# SuperCapacitor_Schmatic_V2.net
KiCad netlist of a schematic drawn in EAGLE
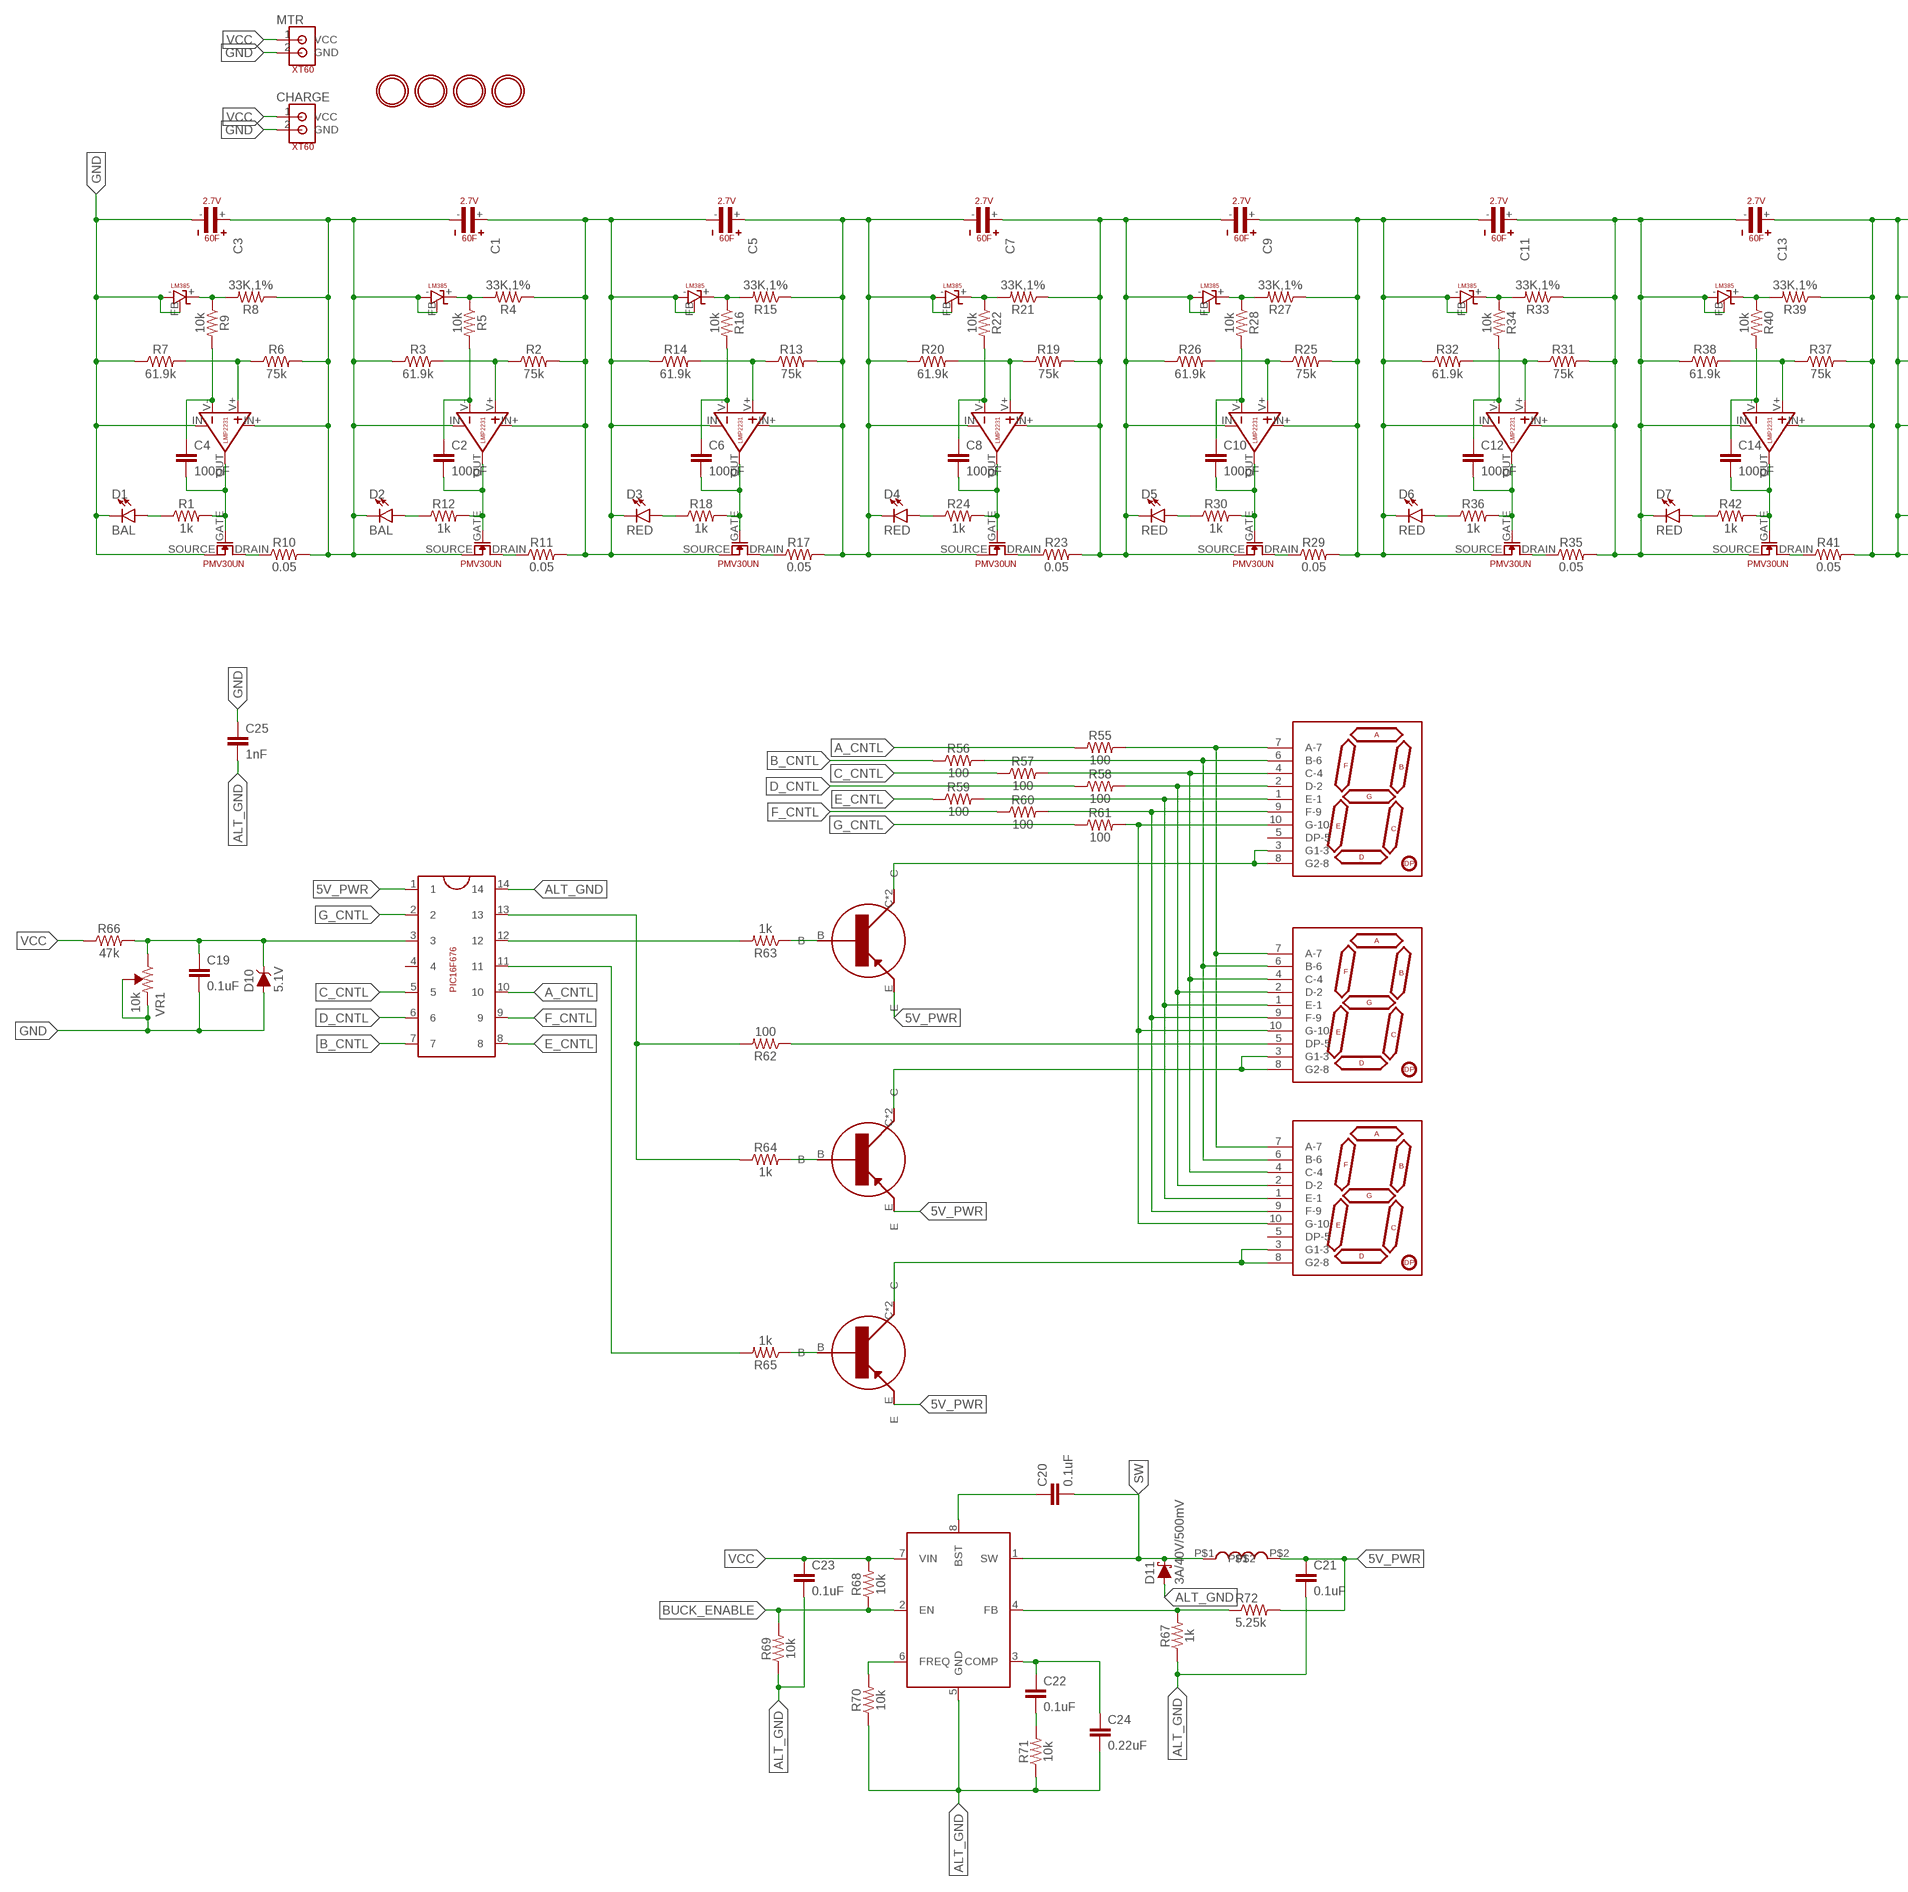
[diagram p0: schematic, sheet 1, part 1 of 2]
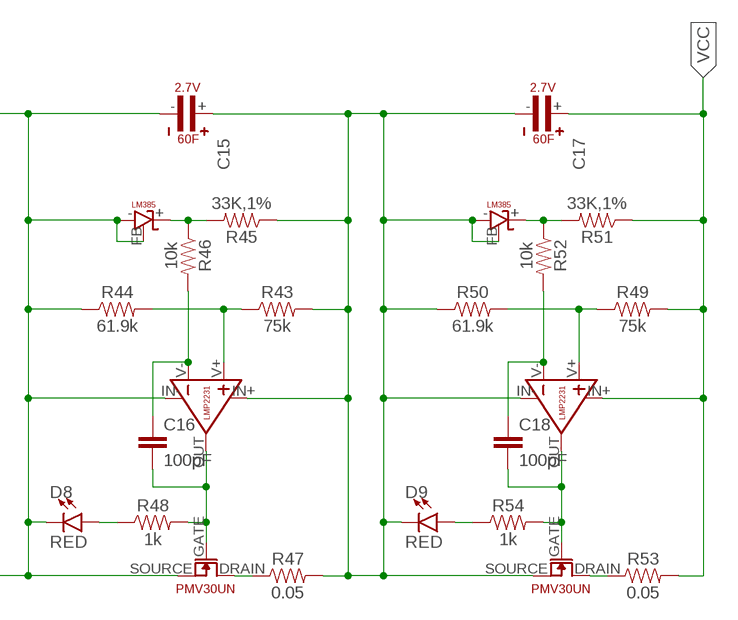
[diagram p1: schematic, sheet 1, part 2 of 2]

(export (version "E")
  (design (tool "Eeschema 10.0.6"))
  (components
    (comp (ref "3.3V_BUCK")
      (value "SOIC8E")
      (footprint "eagle-import:SOIC127P600X170-9N")
      (libsource (lib "eagle-import") (part "SOIC8E"))
    )
    (comp (ref "C1")
      (value "2.7V 60F")
      (footprint "eagle-import:2.7V_60F")
      (libsource (lib "eagle-import") (part "2.7V_60F"))
    )
    (comp (ref "C2")
      (value "100pF")
      (footprint "eagle-import:0603")
      (libsource (lib "eagle-import") (part "100PF-0603-50V-5%"))
    )
    (comp (ref "C3")
      (value "2.7V 60F")
      (footprint "eagle-import:2.7V_60F")
      (libsource (lib "eagle-import") (part "2.7V_60F"))
    )
    (comp (ref "C4")
      (value "100pF")
      (footprint "eagle-import:0603")
      (libsource (lib "eagle-import") (part "100PF-0603-50V-5%"))
    )
    (comp (ref "C5")
      (value "2.7V 60F")
      (footprint "eagle-import:2.7V_60F")
      (libsource (lib "eagle-import") (part "2.7V_60F"))
    )
    (comp (ref "C6")
      (value "100pF")
      (footprint "eagle-import:0603")
      (libsource (lib "eagle-import") (part "100PF-0603-50V-5%"))
    )
    (comp (ref "C7")
      (value "2.7V 60F")
      (footprint "eagle-import:2.7V_60F")
      (libsource (lib "eagle-import") (part "2.7V_60F"))
    )
    (comp (ref "C8")
      (value "100pF")
      (footprint "eagle-import:0603")
      (libsource (lib "eagle-import") (part "100PF-0603-50V-5%"))
    )
    (comp (ref "C9")
      (value "2.7V 60F")
      (footprint "eagle-import:2.7V_60F")
      (libsource (lib "eagle-import") (part "2.7V_60F"))
    )
    (comp (ref "C10")
      (value "100pF")
      (footprint "eagle-import:0603")
      (libsource (lib "eagle-import") (part "100PF-0603-50V-5%"))
    )
    (comp (ref "C11")
      (value "2.7V 60F")
      (footprint "eagle-import:2.7V_60F")
      (libsource (lib "eagle-import") (part "2.7V_60F"))
    )
    (comp (ref "C12")
      (value "100pF")
      (footprint "eagle-import:0603")
      (libsource (lib "eagle-import") (part "100PF-0603-50V-5%"))
    )
    (comp (ref "C13")
      (value "2.7V 60F")
      (footprint "eagle-import:2.7V_60F")
      (libsource (lib "eagle-import") (part "2.7V_60F"))
    )
    (comp (ref "C14")
      (value "100pF")
      (footprint "eagle-import:0603")
      (libsource (lib "eagle-import") (part "100PF-0603-50V-5%"))
    )
    (comp (ref "C15")
      (value "2.7V 60F")
      (footprint "eagle-import:2.7V_60F")
      (libsource (lib "eagle-import") (part "2.7V_60F"))
    )
    (comp (ref "C16")
      (value "100pF")
      (footprint "eagle-import:0603")
      (libsource (lib "eagle-import") (part "100PF-0603-50V-5%"))
    )
    (comp (ref "C17")
      (value "2.7V 60F")
      (footprint "eagle-import:2.7V_60F")
      (libsource (lib "eagle-import") (part "2.7V_60F"))
    )
    (comp (ref "C18")
      (value "100pF")
      (footprint "eagle-import:0603")
      (libsource (lib "eagle-import") (part "100PF-0603-50V-5%"))
    )
    (comp (ref "C19")
      (value "0.1uF")
      (footprint "eagle-import:0603")
      (libsource (lib "eagle-import") (part "SparkFun-Capacitors_510_0.1UF-0603-25V-5%"))
    )
    (comp (ref "C20")
      (value "0.1uF")
      (footprint "eagle-import:0603")
      (libsource (lib "eagle-import") (part "0.1UF-0603-25V-(+80/-20%)"))
    )
    (comp (ref "C21")
      (value "0.1uF")
      (footprint "eagle-import:0603")
      (libsource (lib "eagle-import") (part "0.1UF-0603-25V-(+80/-20%)"))
    )
    (comp (ref "C22")
      (value "0.1uF")
      (footprint "eagle-import:0603")
      (libsource (lib "eagle-import") (part "0.1UF-0603-25V-(+80/-20%)"))
    )
    (comp (ref "C23")
      (value "0.1uF")
      (footprint "eagle-import:0603")
      (libsource (lib "eagle-import") (part "0.1UF-0603-25V-(+80/-20%)"))
    )
    (comp (ref "C24")
      (value "0.22uF")
      (footprint "eagle-import:0603")
      (libsource (lib "eagle-import") (part "0.22UF-0603-50V-(-20/+80%)"))
    )
    (comp (ref "C25")
      (value "1nF")
      (footprint "eagle-import:0603")
      (libsource (lib "eagle-import") (part "1.0NF/1000PF-0603-50V-10%"))
    )
    (comp (ref "CHARGE")
      (value "XT60")
      (footprint "eagle-import:XT60")
      (libsource (lib "eagle-import") (part "XT60"))
    )
    (comp (ref "D1")
      (value "BAL")
      (footprint "eagle-import:LED-0603")
      (libsource (lib "eagle-import") (part "LED-RED0603"))
    )
    (comp (ref "D2")
      (value "BAL")
      (footprint "eagle-import:LED-0603")
      (libsource (lib "eagle-import") (part "LED-RED0603"))
    )
    (comp (ref "D3")
      (value "RED")
      (footprint "eagle-import:LED-0603")
      (libsource (lib "eagle-import") (part "LED-RED0603"))
    )
    (comp (ref "D4")
      (value "RED")
      (footprint "eagle-import:LED-0603")
      (libsource (lib "eagle-import") (part "LED-RED0603"))
    )
    (comp (ref "D5")
      (value "RED")
      (footprint "eagle-import:LED-0603")
      (libsource (lib "eagle-import") (part "LED-RED0603"))
    )
    (comp (ref "D6")
      (value "RED")
      (footprint "eagle-import:LED-0603")
      (libsource (lib "eagle-import") (part "LED-RED0603"))
    )
    (comp (ref "D7")
      (value "RED")
      (footprint "eagle-import:LED-0603")
      (libsource (lib "eagle-import") (part "LED-RED0603"))
    )
    (comp (ref "D8")
      (value "RED")
      (footprint "eagle-import:LED-0603")
      (libsource (lib "eagle-import") (part "LED-RED0603"))
    )
    (comp (ref "D9")
      (value "RED")
      (footprint "eagle-import:LED-0603")
      (libsource (lib "eagle-import") (part "LED-RED0603"))
    )
    (comp (ref "D10")
      (value "5.1V")
      (footprint "eagle-import:SOD-323")
      (libsource (lib "eagle-import") (part "DIODE-ZENER-MMSZ5232BS"))
    )
    (comp (ref "D11")
      (value "3A/40V/500mV")
      (footprint "eagle-import:SMA-DIODE")
      (libsource (lib "eagle-import") (part "DIODE-SCHOTTKY-B340A"))
    )
    (comp (ref "MTR")
      (value "XT60")
      (footprint "eagle-import:XT60")
      (libsource (lib "eagle-import") (part "XT60"))
    )
    (comp (ref "R1")
      (value "1k")
      (footprint "eagle-import:0603")
      (libsource (lib "eagle-import") (part "SparkFun-Resistors_532_1KOHM-0603-1/10W-1%"))
    )
    (comp (ref "R2")
      (value "75k")
      (footprint "eagle-import:0603@1")
      (libsource (lib "eagle-import") (part "75KOHM-0603-1/10W-1%"))
    )
    (comp (ref "R3")
      (value "61.9k")
      (footprint "eagle-import:0603@1")
      (libsource (lib "eagle-import") (part "75KOHM-0603-1/10W-1%"))
    )
    (comp (ref "R4")
      (value "33K,1%")
      (footprint "eagle-import:0603@1")
      (libsource (lib "eagle-import") (part "1MOHM-0603-1/4W-5%"))
    )
    (comp (ref "R5")
      (value "10k")
      (footprint "eagle-import:0603")
      (libsource (lib "eagle-import") (part "10KOHM-0603-1/10W-1%"))
    )
    (comp (ref "R6")
      (value "75k")
      (footprint "eagle-import:0603@1")
      (libsource (lib "eagle-import") (part "75KOHM-0603-1/10W-1%"))
    )
    (comp (ref "R7")
      (value "61.9k")
      (footprint "eagle-import:0603@1")
      (libsource (lib "eagle-import") (part "75KOHM-0603-1/10W-1%"))
    )
    (comp (ref "R8")
      (value "33K,1%")
      (footprint "eagle-import:0603@1")
      (libsource (lib "eagle-import") (part "1MOHM-0603-1/4W-5%"))
    )
    (comp (ref "R9")
      (value "10k")
      (footprint "eagle-import:0603")
      (libsource (lib "eagle-import") (part "10KOHM-0603-1/10W-1%"))
    )
    (comp (ref "R10")
      (value "0.05")
      (footprint "eagle-import:2512")
      (libsource (lib "eagle-import") (part "0.05OHM-2512-3W-1%"))
    )
    (comp (ref "R11")
      (value "0.05")
      (footprint "eagle-import:2512")
      (libsource (lib "eagle-import") (part "0.05OHM-2512-3W-1%"))
    )
    (comp (ref "R12")
      (value "1k")
      (footprint "eagle-import:0603")
      (libsource (lib "eagle-import") (part "SparkFun-Resistors_532_1KOHM-0603-1/10W-1%"))
    )
    (comp (ref "R13")
      (value "75k")
      (footprint "eagle-import:0603@1")
      (libsource (lib "eagle-import") (part "75KOHM-0603-1/10W-1%"))
    )
    (comp (ref "R14")
      (value "61.9k")
      (footprint "eagle-import:0603@1")
      (libsource (lib "eagle-import") (part "75KOHM-0603-1/10W-1%"))
    )
    (comp (ref "R15")
      (value "33K,1%")
      (footprint "eagle-import:0603@1")
      (libsource (lib "eagle-import") (part "1MOHM-0603-1/4W-5%"))
    )
    (comp (ref "R16")
      (value "10k")
      (footprint "eagle-import:0603")
      (libsource (lib "eagle-import") (part "10KOHM-0603-1/10W-1%"))
    )
    (comp (ref "R17")
      (value "0.05")
      (footprint "eagle-import:2512")
      (libsource (lib "eagle-import") (part "0.05OHM-2512-3W-1%"))
    )
    (comp (ref "R18")
      (value "1k")
      (footprint "eagle-import:0603")
      (libsource (lib "eagle-import") (part "SparkFun-Resistors_532_1KOHM-0603-1/10W-1%"))
    )
    (comp (ref "R19")
      (value "75k")
      (footprint "eagle-import:0603@1")
      (libsource (lib "eagle-import") (part "75KOHM-0603-1/10W-1%"))
    )
    (comp (ref "R20")
      (value "61.9k")
      (footprint "eagle-import:0603@1")
      (libsource (lib "eagle-import") (part "75KOHM-0603-1/10W-1%"))
    )
    (comp (ref "R21")
      (value "33K,1%")
      (footprint "eagle-import:0603@1")
      (libsource (lib "eagle-import") (part "1MOHM-0603-1/4W-5%"))
    )
    (comp (ref "R22")
      (value "10k")
      (footprint "eagle-import:0603")
      (libsource (lib "eagle-import") (part "10KOHM-0603-1/10W-1%"))
    )
    (comp (ref "R23")
      (value "0.05")
      (footprint "eagle-import:2512")
      (libsource (lib "eagle-import") (part "0.05OHM-2512-3W-1%"))
    )
    (comp (ref "R24")
      (value "1k")
      (footprint "eagle-import:0603")
      (libsource (lib "eagle-import") (part "SparkFun-Resistors_532_1KOHM-0603-1/10W-1%"))
    )
    (comp (ref "R25")
      (value "75k")
      (footprint "eagle-import:0603@1")
      (libsource (lib "eagle-import") (part "75KOHM-0603-1/10W-1%"))
    )
    (comp (ref "R26")
      (value "61.9k")
      (footprint "eagle-import:0603@1")
      (libsource (lib "eagle-import") (part "75KOHM-0603-1/10W-1%"))
    )
    (comp (ref "R27")
      (value "33K,1%")
      (footprint "eagle-import:0603@1")
      (libsource (lib "eagle-import") (part "1MOHM-0603-1/4W-5%"))
    )
    (comp (ref "R28")
      (value "10k")
      (footprint "eagle-import:0603")
      (libsource (lib "eagle-import") (part "10KOHM-0603-1/10W-1%"))
    )
    (comp (ref "R29")
      (value "0.05")
      (footprint "eagle-import:2512")
      (libsource (lib "eagle-import") (part "0.05OHM-2512-3W-1%"))
    )
    (comp (ref "R30")
      (value "1k")
      (footprint "eagle-import:0603")
      (libsource (lib "eagle-import") (part "SparkFun-Resistors_532_1KOHM-0603-1/10W-1%"))
    )
    (comp (ref "R31")
      (value "75k")
      (footprint "eagle-import:0603@1")
      (libsource (lib "eagle-import") (part "75KOHM-0603-1/10W-1%"))
    )
    (comp (ref "R32")
      (value "61.9k")
      (footprint "eagle-import:0603@1")
      (libsource (lib "eagle-import") (part "75KOHM-0603-1/10W-1%"))
    )
    (comp (ref "R33")
      (value "33K,1%")
      (footprint "eagle-import:0603@1")
      (libsource (lib "eagle-import") (part "1MOHM-0603-1/4W-5%"))
    )
    (comp (ref "R34")
      (value "10k")
      (footprint "eagle-import:0603")
      (libsource (lib "eagle-import") (part "10KOHM-0603-1/10W-1%"))
    )
    (comp (ref "R35")
      (value "0.05")
      (footprint "eagle-import:2512")
      (libsource (lib "eagle-import") (part "0.05OHM-2512-3W-1%"))
    )
    (comp (ref "R36")
      (value "1k")
      (footprint "eagle-import:0603")
      (libsource (lib "eagle-import") (part "SparkFun-Resistors_532_1KOHM-0603-1/10W-1%"))
    )
    (comp (ref "R37")
      (value "75k")
      (footprint "eagle-import:0603@1")
      (libsource (lib "eagle-import") (part "75KOHM-0603-1/10W-1%"))
    )
    (comp (ref "R38")
      (value "61.9k")
      (footprint "eagle-import:0603@1")
      (libsource (lib "eagle-import") (part "75KOHM-0603-1/10W-1%"))
    )
    (comp (ref "R39")
      (value "33K,1%")
      (footprint "eagle-import:0603@1")
      (libsource (lib "eagle-import") (part "1MOHM-0603-1/4W-5%"))
    )
    (comp (ref "R40")
      (value "10k")
      (footprint "eagle-import:0603")
      (libsource (lib "eagle-import") (part "10KOHM-0603-1/10W-1%"))
    )
    (comp (ref "R41")
      (value "0.05")
      (footprint "eagle-import:2512")
      (libsource (lib "eagle-import") (part "0.05OHM-2512-3W-1%"))
    )
    (comp (ref "R42")
      (value "1k")
      (footprint "eagle-import:0603")
      (libsource (lib "eagle-import") (part "SparkFun-Resistors_532_1KOHM-0603-1/10W-1%"))
    )
    (comp (ref "R43")
      (value "75k")
      (footprint "eagle-import:0603@1")
      (libsource (lib "eagle-import") (part "75KOHM-0603-1/10W-1%"))
    )
    (comp (ref "R44")
      (value "61.9k")
      (footprint "eagle-import:0603@1")
      (libsource (lib "eagle-import") (part "75KOHM-0603-1/10W-1%"))
    )
    (comp (ref "R45")
      (value "33K,1%")
      (footprint "eagle-import:0603@1")
      (libsource (lib "eagle-import") (part "1MOHM-0603-1/4W-5%"))
    )
    (comp (ref "R46")
      (value "10k")
      (footprint "eagle-import:0603")
      (libsource (lib "eagle-import") (part "10KOHM-0603-1/10W-1%"))
    )
    (comp (ref "R47")
      (value "0.05")
      (footprint "eagle-import:2512")
      (libsource (lib "eagle-import") (part "0.05OHM-2512-3W-1%"))
    )
    (comp (ref "R48")
      (value "1k")
      (footprint "eagle-import:0603")
      (libsource (lib "eagle-import") (part "SparkFun-Resistors_532_1KOHM-0603-1/10W-1%"))
    )
    (comp (ref "R49")
      (value "75k")
      (footprint "eagle-import:0603@1")
      (libsource (lib "eagle-import") (part "75KOHM-0603-1/10W-1%"))
    )
    (comp (ref "R50")
      (value "61.9k")
      (footprint "eagle-import:0603@1")
      (libsource (lib "eagle-import") (part "75KOHM-0603-1/10W-1%"))
    )
    (comp (ref "R51")
      (value "33K,1%")
      (footprint "eagle-import:0603@1")
      (libsource (lib "eagle-import") (part "1MOHM-0603-1/4W-5%"))
    )
    (comp (ref "R52")
      (value "10k")
      (footprint "eagle-import:0603")
      (libsource (lib "eagle-import") (part "10KOHM-0603-1/10W-1%"))
    )
    (comp (ref "R53")
      (value "0.05")
      (footprint "eagle-import:2512")
      (libsource (lib "eagle-import") (part "0.05OHM-2512-3W-1%"))
    )
    (comp (ref "R54")
      (value "1k")
      (footprint "eagle-import:0603")
      (libsource (lib "eagle-import") (part "SparkFun-Resistors_532_1KOHM-0603-1/10W-1%"))
    )
    (comp (ref "R55")
      (value "100")
      (footprint "eagle-import:0603")
      (libsource (lib "eagle-import") (part "100OHM-0603-1/4W-5%"))
    )
    (comp (ref "R56")
      (value "100")
      (footprint "eagle-import:0603")
      (libsource (lib "eagle-import") (part "100OHM-0603-1/4W-5%"))
    )
    (comp (ref "R57")
      (value "100")
      (footprint "eagle-import:0603")
      (libsource (lib "eagle-import") (part "100OHM-0603-1/4W-5%"))
    )
    (comp (ref "R58")
      (value "100")
      (footprint "eagle-import:0603")
      (libsource (lib "eagle-import") (part "100OHM-0603-1/4W-5%"))
    )
    (comp (ref "R59")
      (value "100")
      (footprint "eagle-import:0603")
      (libsource (lib "eagle-import") (part "100OHM-0603-1/4W-5%"))
    )
    (comp (ref "R60")
      (value "100")
      (footprint "eagle-import:0603")
      (libsource (lib "eagle-import") (part "100OHM-0603-1/4W-5%"))
    )
    (comp (ref "R61")
      (value "100")
      (footprint "eagle-import:0603")
      (libsource (lib "eagle-import") (part "100OHM-0603-1/4W-5%"))
    )
    (comp (ref "R62")
      (value "100")
      (footprint "eagle-import:0603")
      (libsource (lib "eagle-import") (part "100OHM-0603-1/4W-5%"))
    )
    (comp (ref "R63")
      (value "1k")
      (footprint "eagle-import:0603")
      (libsource (lib "eagle-import") (part "SparkFun-Resistors_532_1KOHM-0603-1/10W-1%"))
    )
    (comp (ref "R64")
      (value "1k")
      (footprint "eagle-import:0603")
      (libsource (lib "eagle-import") (part "SparkFun-Resistors_532_1KOHM-0603-1/10W-1%"))
    )
    (comp (ref "R65")
      (value "1k")
      (footprint "eagle-import:0603")
      (libsource (lib "eagle-import") (part "SparkFun-Resistors_532_1KOHM-0603-1/10W-1%"))
    )
    (comp (ref "R66")
      (value "47k")
      (footprint "eagle-import:0603")
      (libsource (lib "eagle-import") (part "47KOHM-0603-1/10W-1%"))
    )
    (comp (ref "R67")
      (value "1k")
      (footprint "eagle-import:0603")
      (libsource (lib "eagle-import") (part "1KOHM-0603-1/10W-1%"))
    )
    (comp (ref "R68")
      (value "10k")
      (footprint "eagle-import:0603")
      (libsource (lib "eagle-import") (part "10KOHM-0603-1/10W-1%"))
    )
    (comp (ref "R69")
      (value "10k")
      (footprint "eagle-import:0603")
      (libsource (lib "eagle-import") (part "10KOHM-0603-1/10W-1%"))
    )
    (comp (ref "R70")
      (value "10k")
      (footprint "eagle-import:0603")
      (libsource (lib "eagle-import") (part "10KOHM-0603-1/10W-1%"))
    )
    (comp (ref "R71")
      (value "10k")
      (footprint "eagle-import:0603")
      (libsource (lib "eagle-import") (part "10KOHM-0603-1/10W-1%"))
    )
    (comp (ref "R72")
      (value "5.25k")
      (footprint "eagle-import:RES_0805")
      (fields
        (field (name "DIGIKEY_PART_NUMBER") "541-0.0ATR-ND")
        (field (name "MANUFACTURER") "Vishay Dale")
        (field (name "MPN") "CRCW08050000Z0EA")
        (field (name "CREATED_BY") "PCBLayout.com")
      )
      (libsource (lib "eagle-import") (part "CRCW08050000Z0EA"))
    )
    (comp (ref "U$1")
      (value "LMP2231")
      (footprint "eagle-import:LMP2231_SOT23_5")
      (libsource (lib "eagle-import") (part "LMP2231"))
    )
    (comp (ref "U$2")
      (value "LM385")
      (footprint "eagle-import:LM385_SOT23")
      (libsource (lib "eagle-import") (part "LM385"))
    )
    (comp (ref "U$3")
      (value "PMV30UN_MOS")
      (footprint "eagle-import:PMV30UN_SOT23")
      (libsource (lib "eagle-import") (part "PMV30UN_MOS"))
    )
    (comp (ref "U$4")
      (value "LMP2231")
      (footprint "eagle-import:LMP2231_SOT23_5")
      (libsource (lib "eagle-import") (part "LMP2231"))
    )
    (comp (ref "U$5")
      (value "LM385")
      (footprint "eagle-import:LM385_SOT23")
      (libsource (lib "eagle-import") (part "LM385"))
    )
    (comp (ref "U$6")
      (value "PMV30UN_MOS")
      (footprint "eagle-import:PMV30UN_SOT23")
      (libsource (lib "eagle-import") (part "PMV30UN_MOS"))
    )
    (comp (ref "U$7")
      (value "LMP2231")
      (footprint "eagle-import:LMP2231_SOT23_5")
      (libsource (lib "eagle-import") (part "LMP2231"))
    )
    (comp (ref "U$8")
      (value "LM385")
      (footprint "eagle-import:LM385_SOT23")
      (libsource (lib "eagle-import") (part "LM385"))
    )
    (comp (ref "U$9")
      (value "PMV30UN_MOS")
      (footprint "eagle-import:PMV30UN_SOT23")
      (libsource (lib "eagle-import") (part "PMV30UN_MOS"))
    )
    (comp (ref "U$10")
      (value "LMP2231")
      (footprint "eagle-import:LMP2231_SOT23_5")
      (libsource (lib "eagle-import") (part "LMP2231"))
    )
    (comp (ref "U$11")
      (value "LM385")
      (footprint "eagle-import:LM385_SOT23")
      (libsource (lib "eagle-import") (part "LM385"))
    )
    (comp (ref "U$12")
      (value "PMV30UN_MOS")
      (footprint "eagle-import:PMV30UN_SOT23")
      (libsource (lib "eagle-import") (part "PMV30UN_MOS"))
    )
    (comp (ref "U$13")
      (value "LMP2231")
      (footprint "eagle-import:LMP2231_SOT23_5")
      (libsource (lib "eagle-import") (part "LMP2231"))
    )
    (comp (ref "U$14")
      (value "LM385")
      (footprint "eagle-import:LM385_SOT23")
      (libsource (lib "eagle-import") (part "LM385"))
    )
    (comp (ref "U$15")
      (value "PMV30UN_MOS")
      (footprint "eagle-import:PMV30UN_SOT23")
      (libsource (lib "eagle-import") (part "PMV30UN_MOS"))
    )
    (comp (ref "U$16")
      (value "LMP2231")
      (footprint "eagle-import:LMP2231_SOT23_5")
      (libsource (lib "eagle-import") (part "LMP2231"))
    )
    (comp (ref "U$17")
      (value "LM385")
      (footprint "eagle-import:LM385_SOT23")
      (libsource (lib "eagle-import") (part "LM385"))
    )
    (comp (ref "U$18")
      (value "PMV30UN_MOS")
      (footprint "eagle-import:PMV30UN_SOT23")
      (libsource (lib "eagle-import") (part "PMV30UN_MOS"))
    )
    (comp (ref "U$19")
      (value "LMP2231")
      (footprint "eagle-import:LMP2231_SOT23_5")
      (libsource (lib "eagle-import") (part "LMP2231"))
    )
    (comp (ref "U$20")
      (value "LM385")
      (footprint "eagle-import:LM385_SOT23")
      (libsource (lib "eagle-import") (part "LM385"))
    )
    (comp (ref "U$21")
      (value "PMV30UN_MOS")
      (footprint "eagle-import:PMV30UN_SOT23")
      (libsource (lib "eagle-import") (part "PMV30UN_MOS"))
    )
    (comp (ref "U$22")
      (value "LMP2231")
      (footprint "eagle-import:LMP2231_SOT23_5")
      (libsource (lib "eagle-import") (part "LMP2231"))
    )
    (comp (ref "U$23")
      (value "LM385")
      (footprint "eagle-import:LM385_SOT23")
      (libsource (lib "eagle-import") (part "LM385"))
    )
    (comp (ref "U$24")
      (value "PMV30UN_MOS")
      (footprint "eagle-import:PMV30UN_SOT23")
      (libsource (lib "eagle-import") (part "PMV30UN_MOS"))
    )
    (comp (ref "U$25")
      (value "LMP2231")
      (footprint "eagle-import:LMP2231_SOT23_5")
      (libsource (lib "eagle-import") (part "LMP2231"))
    )
    (comp (ref "U$26")
      (value "LM385")
      (footprint "eagle-import:LM385_SOT23")
      (libsource (lib "eagle-import") (part "LM385"))
    )
    (comp (ref "U$27")
      (value "PMV30UN_MOS")
      (footprint "eagle-import:PMV30UN_SOT23")
      (libsource (lib "eagle-import") (part "PMV30UN_MOS"))
    )
    (comp (ref "U$28")
      (value "PZT3906")
      (footprint "eagle-import:SOT_223")
      (libsource (lib "eagle-import") (part "PZT3906"))
    )
    (comp (ref "U$29")
      (value "PZT3906")
      (footprint "eagle-import:SOT_223")
      (libsource (lib "eagle-import") (part "PZT3906"))
    )
    (comp (ref "U$30")
      (value "M5")
      (footprint "eagle-import:M5")
      (libsource (lib "eagle-import") (part "M5"))
    )
    (comp (ref "U$31")
      (value "M5")
      (footprint "eagle-import:M5")
      (libsource (lib "eagle-import") (part "M5"))
    )
    (comp (ref "U$32")
      (value "M5")
      (footprint "eagle-import:M5")
      (libsource (lib "eagle-import") (part "M5"))
    )
    (comp (ref "U$33")
      (value "M5")
      (footprint "eagle-import:M5")
      (libsource (lib "eagle-import") (part "M5"))
    )
    (comp (ref "U$34")
      (value "PZT3906")
      (footprint "eagle-import:SOT_223")
      (libsource (lib "eagle-import") (part "PZT3906"))
    )
    (comp (ref "U$35")
      (value "DSM7T")
      (footprint "eagle-import:7-SEGMENT_SMD")
      (libsource (lib "eagle-import") (part "DSM7T"))
    )
    (comp (ref "U$36")
      (value "DSM7T")
      (footprint "eagle-import:7-SEGMENT_SMD")
      (libsource (lib "eagle-import") (part "DSM7T"))
    )
    (comp (ref "U$37")
      (value "DSM7T")
      (footprint "eagle-import:7-SEGMENT_SMD")
      (libsource (lib "eagle-import") (part "DSM7T"))
    )
    (comp (ref "U$38")
      (value "PIC16F676")
      (footprint "eagle-import:PIC16F676")
      (libsource (lib "eagle-import") (part "PIC16F676"))
    )
    (comp (ref "U$39")
      (value "4.7UH_INDUCTOR")
      (footprint "eagle-import:4.7UH_INDUCTOR")
      (libsource (lib "eagle-import") (part "4.7UH_INDUCTOR"))
    )
    (comp (ref "VR1")
      (value "10k")
      (footprint "eagle-import:TRIMPOT-SMD-TC33X")
      (libsource (lib "eagle-import") (part "TRIMPOT-SMD-3MM-OPEN-1/10W-25%"))
    )
  )
  (nets
    (net (code "1") (name "5V_PWR") (class "Default")
      (node (ref "C21") (pin "1") (pinfunction "1_1") (pintype "passive"))
      (node (ref "R72") (pin "2") (pinfunction "2_2") (pintype "passive"))
      (node (ref "U$28") (pin "E") (pinfunction "E_E") (pintype "bidirectional"))
      (node (ref "U$29") (pin "E") (pinfunction "E_E") (pintype "bidirectional"))
      (node (ref "U$34") (pin "E") (pinfunction "E_E") (pintype "bidirectional"))
      (node (ref "U$38") (pin "1") (pinfunction "1_1") (pintype "bidirectional"))
      (node (ref "U$39") (pin "P$2") (pinfunction "P$2_P$2") (pintype "bidirectional"))
    )
    (net (code "2") (name "ALT_GND") (class "Default")
      (node (ref "3.3V_BUCK") (pin "5") (pinfunction "GND_5") (pintype "bidirectional"))
      (node (ref "C21") (pin "2") (pinfunction "2_2") (pintype "passive"))
      (node (ref "C23") (pin "2") (pinfunction "2_2") (pintype "passive"))
      (node (ref "C24") (pin "2") (pinfunction "2_2") (pintype "passive"))
      (node (ref "C25") (pin "2") (pinfunction "2_2") (pintype "passive"))
      (node (ref "D11") (pin "A") (pinfunction "A_A") (pintype "passive"))
      (node (ref "R67") (pin "1") (pinfunction "1_1") (pintype "passive"))
      (node (ref "R69") (pin "1") (pinfunction "1_1") (pintype "passive"))
      (node (ref "R70") (pin "1") (pinfunction "1_1") (pintype "passive"))
      (node (ref "R71") (pin "1") (pinfunction "1_1") (pintype "passive"))
      (node (ref "U$38") (pin "14") (pinfunction "14_14") (pintype "bidirectional"))
    )
    (net (code "3") (name "A_CNTL") (class "Default")
      (node (ref "R55") (pin "1") (pinfunction "1_1") (pintype "passive"))
      (node (ref "U$38") (pin "10") (pinfunction "10_10") (pintype "bidirectional"))
    )
    (net (code "4") (name "BUCK_ENABLE") (class "Default")
      (node (ref "3.3V_BUCK") (pin "2") (pinfunction "EN_2") (pintype "bidirectional"))
      (node (ref "R68") (pin "1") (pinfunction "1_1") (pintype "passive"))
      (node (ref "R69") (pin "2") (pinfunction "2_2") (pintype "passive"))
    )
    (net (code "5") (name "B_CNTL") (class "Default")
      (node (ref "R56") (pin "1") (pinfunction "1_1") (pintype "passive"))
      (node (ref "U$38") (pin "7") (pinfunction "7_7") (pintype "bidirectional"))
    )
    (net (code "6") (name "C_CNTL") (class "Default")
      (node (ref "R57") (pin "1") (pinfunction "1_1") (pintype "passive"))
      (node (ref "U$38") (pin "5") (pinfunction "5_5") (pintype "bidirectional"))
    )
    (net (code "7") (name "D_CNTL") (class "Default")
      (node (ref "R58") (pin "1") (pinfunction "1_1") (pintype "passive"))
      (node (ref "U$38") (pin "6") (pinfunction "6_6") (pintype "bidirectional"))
    )
    (net (code "8") (name "E_CNTL") (class "Default")
      (node (ref "R59") (pin "1") (pinfunction "1_1") (pintype "passive"))
      (node (ref "U$38") (pin "8") (pinfunction "8_8") (pintype "bidirectional"))
    )
    (net (code "9") (name "F_CNTL") (class "Default")
      (node (ref "R60") (pin "1") (pinfunction "1_1") (pintype "passive"))
      (node (ref "U$38") (pin "9") (pinfunction "9_9") (pintype "bidirectional"))
    )
    (net (code "10") (name "GND") (class "Default")
      (node (ref "C19") (pin "2") (pinfunction "2_2") (pintype "passive"))
      (node (ref "C25") (pin "1") (pinfunction "1_1") (pintype "passive"))
      (node (ref "C3") (pin "-") (pinfunction "-_-") (pintype "bidirectional"))
      (node (ref "CHARGE") (pin "2") (pinfunction "GND_2") (pintype "bidirectional"))
      (node (ref "D1") (pin "C") (pinfunction "C_C") (pintype "passive"))
      (node (ref "D10") (pin "A") (pinfunction "A_A") (pintype "passive"))
      (node (ref "MTR") (pin "2") (pinfunction "GND_2") (pintype "bidirectional"))
      (node (ref "R7") (pin "1") (pinfunction "1_1") (pintype "passive"))
      (node (ref "U$4") (pin "IN-") (pinfunction "IN-_IN-") (pintype "bidirectional"))
      (node (ref "U$5") (pin "-") (pinfunction "-_-") (pintype "bidirectional"))
      (node (ref "U$5") (pin "FB") (pinfunction "FB_FB") (pintype "bidirectional"))
      (node (ref "U$6") (pin "SOURCE") (pinfunction "SOURCE_SOURCE") (pintype "bidirectional"))
      (node (ref "VR1") (pin "2") (pinfunction "WIPER_2") (pintype "passive"))
      (node (ref "VR1") (pin "3") (pinfunction "CCW_3") (pintype "passive"))
    )
    (net (code "11") (name "G_CNTL") (class "Default")
      (node (ref "R61") (pin "1") (pinfunction "1_1") (pintype "passive"))
      (node (ref "U$38") (pin "2") (pinfunction "2_2") (pintype "bidirectional"))
    )
    (net (code "12") (name "Net-(3.3V_BUCK-BST)") (class "Default")
      (node (ref "3.3V_BUCK") (pin "8") (pinfunction "BST_8") (pintype "bidirectional"))
      (node (ref "C20") (pin "1") (pinfunction "1_1") (pintype "passive"))
    )
    (net (code "13") (name "Net-(3.3V_BUCK-COMP)") (class "Default")
      (node (ref "3.3V_BUCK") (pin "3") (pinfunction "COMP_3") (pintype "bidirectional"))
      (node (ref "C22") (pin "1") (pinfunction "1_1") (pintype "passive"))
      (node (ref "C24") (pin "1") (pinfunction "1_1") (pintype "passive"))
    )
    (net (code "14") (name "Net-(3.3V_BUCK-FB)") (class "Default")
      (node (ref "3.3V_BUCK") (pin "4") (pinfunction "FB_4") (pintype "bidirectional"))
      (node (ref "R67") (pin "2") (pinfunction "2_2") (pintype "passive"))
      (node (ref "R72") (pin "1") (pinfunction "1_1") (pintype "passive"))
    )
    (net (code "15") (name "Net-(3.3V_BUCK-FREQ)") (class "Default")
      (node (ref "3.3V_BUCK") (pin "6") (pinfunction "FREQ_6") (pintype "bidirectional"))
      (node (ref "R70") (pin "2") (pinfunction "2_2") (pintype "passive"))
    )
    (net (code "16") (name "Net-(C2-Pad1)") (class "Default")
      (node (ref "C2") (pin "1") (pinfunction "1_1") (pintype "passive"))
      (node (ref "R5") (pin "2") (pinfunction "2_2") (pintype "passive"))
      (node (ref "U$1") (pin "V-") (pinfunction "V-_V-") (pintype "bidirectional"))
    )
    (net (code "17") (name "Net-(C2-Pad2)") (class "Default")
      (node (ref "C2") (pin "2") (pinfunction "2_2") (pintype "passive"))
      (node (ref "R12") (pin "2") (pinfunction "2_2") (pintype "passive"))
      (node (ref "U$1") (pin "OUT") (pinfunction "OUT_OUT") (pintype "bidirectional"))
      (node (ref "U$3") (pin "GATE") (pinfunction "GATE_GATE") (pintype "bidirectional"))
    )
    (net (code "18") (name "Net-(C4-Pad1)") (class "Default")
      (node (ref "C4") (pin "1") (pinfunction "1_1") (pintype "passive"))
      (node (ref "R9") (pin "2") (pinfunction "2_2") (pintype "passive"))
      (node (ref "U$4") (pin "V-") (pinfunction "V-_V-") (pintype "bidirectional"))
    )
    (net (code "19") (name "Net-(C4-Pad2)") (class "Default")
      (node (ref "C4") (pin "2") (pinfunction "2_2") (pintype "passive"))
      (node (ref "R1") (pin "2") (pinfunction "2_2") (pintype "passive"))
      (node (ref "U$4") (pin "OUT") (pinfunction "OUT_OUT") (pintype "bidirectional"))
      (node (ref "U$6") (pin "GATE") (pinfunction "GATE_GATE") (pintype "bidirectional"))
    )
    (net (code "20") (name "Net-(C6-Pad1)") (class "Default")
      (node (ref "C6") (pin "1") (pinfunction "1_1") (pintype "passive"))
      (node (ref "R16") (pin "2") (pinfunction "2_2") (pintype "passive"))
      (node (ref "U$7") (pin "V-") (pinfunction "V-_V-") (pintype "bidirectional"))
    )
    (net (code "21") (name "Net-(C6-Pad2)") (class "Default")
      (node (ref "C6") (pin "2") (pinfunction "2_2") (pintype "passive"))
      (node (ref "R18") (pin "2") (pinfunction "2_2") (pintype "passive"))
      (node (ref "U$7") (pin "OUT") (pinfunction "OUT_OUT") (pintype "bidirectional"))
      (node (ref "U$9") (pin "GATE") (pinfunction "GATE_GATE") (pintype "bidirectional"))
    )
    (net (code "22") (name "Net-(C8-Pad1)") (class "Default")
      (node (ref "C8") (pin "1") (pinfunction "1_1") (pintype "passive"))
      (node (ref "R22") (pin "2") (pinfunction "2_2") (pintype "passive"))
      (node (ref "U$10") (pin "V-") (pinfunction "V-_V-") (pintype "bidirectional"))
    )
    (net (code "23") (name "Net-(C8-Pad2)") (class "Default")
      (node (ref "C8") (pin "2") (pinfunction "2_2") (pintype "passive"))
      (node (ref "R24") (pin "2") (pinfunction "2_2") (pintype "passive"))
      (node (ref "U$10") (pin "OUT") (pinfunction "OUT_OUT") (pintype "bidirectional"))
      (node (ref "U$12") (pin "GATE") (pinfunction "GATE_GATE") (pintype "bidirectional"))
    )
    (net (code "24") (name "Net-(C10-Pad1)") (class "Default")
      (node (ref "C10") (pin "1") (pinfunction "1_1") (pintype "passive"))
      (node (ref "R28") (pin "2") (pinfunction "2_2") (pintype "passive"))
      (node (ref "U$13") (pin "V-") (pinfunction "V-_V-") (pintype "bidirectional"))
    )
    (net (code "25") (name "Net-(C10-Pad2)") (class "Default")
      (node (ref "C10") (pin "2") (pinfunction "2_2") (pintype "passive"))
      (node (ref "R30") (pin "2") (pinfunction "2_2") (pintype "passive"))
      (node (ref "U$13") (pin "OUT") (pinfunction "OUT_OUT") (pintype "bidirectional"))
      (node (ref "U$15") (pin "GATE") (pinfunction "GATE_GATE") (pintype "bidirectional"))
    )
    (net (code "26") (name "Net-(C12-Pad1)") (class "Default")
      (node (ref "C12") (pin "1") (pinfunction "1_1") (pintype "passive"))
      (node (ref "R34") (pin "2") (pinfunction "2_2") (pintype "passive"))
      (node (ref "U$16") (pin "V-") (pinfunction "V-_V-") (pintype "bidirectional"))
    )
    (net (code "27") (name "Net-(C12-Pad2)") (class "Default")
      (node (ref "C12") (pin "2") (pinfunction "2_2") (pintype "passive"))
      (node (ref "R36") (pin "2") (pinfunction "2_2") (pintype "passive"))
      (node (ref "U$16") (pin "OUT") (pinfunction "OUT_OUT") (pintype "bidirectional"))
      (node (ref "U$18") (pin "GATE") (pinfunction "GATE_GATE") (pintype "bidirectional"))
    )
    (net (code "28") (name "Net-(C14-Pad1)") (class "Default")
      (node (ref "C14") (pin "1") (pinfunction "1_1") (pintype "passive"))
      (node (ref "R40") (pin "2") (pinfunction "2_2") (pintype "passive"))
      (node (ref "U$19") (pin "V-") (pinfunction "V-_V-") (pintype "bidirectional"))
    )
    (net (code "29") (name "Net-(C14-Pad2)") (class "Default")
      (node (ref "C14") (pin "2") (pinfunction "2_2") (pintype "passive"))
      (node (ref "R42") (pin "2") (pinfunction "2_2") (pintype "passive"))
      (node (ref "U$19") (pin "OUT") (pinfunction "OUT_OUT") (pintype "bidirectional"))
      (node (ref "U$21") (pin "GATE") (pinfunction "GATE_GATE") (pintype "bidirectional"))
    )
    (net (code "30") (name "Net-(C16-Pad1)") (class "Default")
      (node (ref "C16") (pin "1") (pinfunction "1_1") (pintype "passive"))
      (node (ref "R46") (pin "2") (pinfunction "2_2") (pintype "passive"))
      (node (ref "U$22") (pin "V-") (pinfunction "V-_V-") (pintype "bidirectional"))
    )
    (net (code "31") (name "Net-(C16-Pad2)") (class "Default")
      (node (ref "C16") (pin "2") (pinfunction "2_2") (pintype "passive"))
      (node (ref "R48") (pin "2") (pinfunction "2_2") (pintype "passive"))
      (node (ref "U$22") (pin "OUT") (pinfunction "OUT_OUT") (pintype "bidirectional"))
      (node (ref "U$24") (pin "GATE") (pinfunction "GATE_GATE") (pintype "bidirectional"))
    )
    (net (code "32") (name "Net-(C18-Pad1)") (class "Default")
      (node (ref "C18") (pin "1") (pinfunction "1_1") (pintype "passive"))
      (node (ref "R52") (pin "2") (pinfunction "2_2") (pintype "passive"))
      (node (ref "U$25") (pin "V-") (pinfunction "V-_V-") (pintype "bidirectional"))
    )
    (net (code "33") (name "Net-(C18-Pad2)") (class "Default")
      (node (ref "C18") (pin "2") (pinfunction "2_2") (pintype "passive"))
      (node (ref "R54") (pin "2") (pinfunction "2_2") (pintype "passive"))
      (node (ref "U$25") (pin "OUT") (pinfunction "OUT_OUT") (pintype "bidirectional"))
      (node (ref "U$27") (pin "GATE") (pinfunction "GATE_GATE") (pintype "bidirectional"))
    )
    (net (code "34") (name "Net-(C22-Pad2)") (class "Default")
      (node (ref "C22") (pin "2") (pinfunction "2_2") (pintype "passive"))
      (node (ref "R71") (pin "2") (pinfunction "2_2") (pintype "passive"))
    )
    (net (code "35") (name "Net-(D1-PadA)") (class "Default")
      (node (ref "D1") (pin "A") (pinfunction "A_A") (pintype "passive"))
      (node (ref "R1") (pin "1") (pinfunction "1_1") (pintype "passive"))
    )
    (net (code "36") (name "Net-(D2-PadA)") (class "Default")
      (node (ref "D2") (pin "A") (pinfunction "A_A") (pintype "passive"))
      (node (ref "R12") (pin "1") (pinfunction "1_1") (pintype "passive"))
    )
    (net (code "37") (name "Net-(D3-PadA)") (class "Default")
      (node (ref "D3") (pin "A") (pinfunction "A_A") (pintype "passive"))
      (node (ref "R18") (pin "1") (pinfunction "1_1") (pintype "passive"))
    )
    (net (code "38") (name "Net-(D4-PadA)") (class "Default")
      (node (ref "D4") (pin "A") (pinfunction "A_A") (pintype "passive"))
      (node (ref "R24") (pin "1") (pinfunction "1_1") (pintype "passive"))
    )
    (net (code "39") (name "Net-(D5-PadA)") (class "Default")
      (node (ref "D5") (pin "A") (pinfunction "A_A") (pintype "passive"))
      (node (ref "R30") (pin "1") (pinfunction "1_1") (pintype "passive"))
    )
    (net (code "40") (name "Net-(D6-PadA)") (class "Default")
      (node (ref "D6") (pin "A") (pinfunction "A_A") (pintype "passive"))
      (node (ref "R36") (pin "1") (pinfunction "1_1") (pintype "passive"))
    )
    (net (code "41") (name "Net-(D7-PadA)") (class "Default")
      (node (ref "D7") (pin "A") (pinfunction "A_A") (pintype "passive"))
      (node (ref "R42") (pin "1") (pinfunction "1_1") (pintype "passive"))
    )
    (net (code "42") (name "Net-(D8-PadA)") (class "Default")
      (node (ref "D8") (pin "A") (pinfunction "A_A") (pintype "passive"))
      (node (ref "R48") (pin "1") (pinfunction "1_1") (pintype "passive"))
    )
    (net (code "43") (name "Net-(D9-PadA)") (class "Default")
      (node (ref "D9") (pin "A") (pinfunction "A_A") (pintype "passive"))
      (node (ref "R54") (pin "1") (pinfunction "1_1") (pintype "passive"))
    )
    (net (code "44") (name "Net-(R2-Pad1)") (class "Default")
      (node (ref "R2") (pin "1") (pinfunction "1_1") (pintype "passive"))
      (node (ref "R3") (pin "2") (pinfunction "2_2") (pintype "passive"))
      (node (ref "U$1") (pin "V+") (pinfunction "V+_V+") (pintype "bidirectional"))
    )
    (net (code "45") (name "Net-(R4-Pad2)") (class "Default")
      (node (ref "R4") (pin "2") (pinfunction "2_2") (pintype "passive"))
      (node (ref "R5") (pin "1") (pinfunction "1_1") (pintype "passive"))
      (node (ref "U$2") (pin "+") (pinfunction "+_+") (pintype "bidirectional"))
    )
    (net (code "46") (name "Net-(R6-Pad1)") (class "Default")
      (node (ref "R6") (pin "1") (pinfunction "1_1") (pintype "passive"))
      (node (ref "R7") (pin "2") (pinfunction "2_2") (pintype "passive"))
      (node (ref "U$4") (pin "V+") (pinfunction "V+_V+") (pintype "bidirectional"))
    )
    (net (code "47") (name "Net-(R8-Pad2)") (class "Default")
      (node (ref "R8") (pin "2") (pinfunction "2_2") (pintype "passive"))
      (node (ref "R9") (pin "1") (pinfunction "1_1") (pintype "passive"))
      (node (ref "U$5") (pin "+") (pinfunction "+_+") (pintype "bidirectional"))
    )
    (net (code "48") (name "Net-(R10-1)") (class "Default")
      (node (ref "R10") (pin "P$1") (pinfunction "1_P$1") (pintype "passive"))
      (node (ref "U$6") (pin "DRAIN") (pinfunction "DRAIN_DRAIN") (pintype "bidirectional"))
    )
    (net (code "49") (name "Net-(R10-2)") (class "Default")
      (node (ref "C1") (pin "-") (pinfunction "-_-") (pintype "bidirectional"))
      (node (ref "C3") (pin "+") (pinfunction "+_+") (pintype "bidirectional"))
      (node (ref "D2") (pin "C") (pinfunction "C_C") (pintype "passive"))
      (node (ref "R10") (pin "P$2") (pinfunction "2_P$2") (pintype "passive"))
      (node (ref "R3") (pin "1") (pinfunction "1_1") (pintype "passive"))
      (node (ref "R6") (pin "2") (pinfunction "2_2") (pintype "passive"))
      (node (ref "R8") (pin "1") (pinfunction "1_1") (pintype "passive"))
      (node (ref "U$1") (pin "IN-") (pinfunction "IN-_IN-") (pintype "bidirectional"))
      (node (ref "U$2") (pin "-") (pinfunction "-_-") (pintype "bidirectional"))
      (node (ref "U$2") (pin "FB") (pinfunction "FB_FB") (pintype "bidirectional"))
      (node (ref "U$3") (pin "SOURCE") (pinfunction "SOURCE_SOURCE") (pintype "bidirectional"))
      (node (ref "U$4") (pin "IN+") (pinfunction "IN+_IN+") (pintype "bidirectional"))
    )
    (net (code "50") (name "Net-(R11-1)") (class "Default")
      (node (ref "R11") (pin "P$1") (pinfunction "1_P$1") (pintype "passive"))
      (node (ref "U$3") (pin "DRAIN") (pinfunction "DRAIN_DRAIN") (pintype "bidirectional"))
    )
    (net (code "51") (name "Net-(R11-2)") (class "Default")
      (node (ref "C1") (pin "+") (pinfunction "+_+") (pintype "bidirectional"))
      (node (ref "C5") (pin "-") (pinfunction "-_-") (pintype "bidirectional"))
      (node (ref "D3") (pin "C") (pinfunction "C_C") (pintype "passive"))
      (node (ref "R11") (pin "P$2") (pinfunction "2_P$2") (pintype "passive"))
      (node (ref "R14") (pin "1") (pinfunction "1_1") (pintype "passive"))
      (node (ref "R2") (pin "2") (pinfunction "2_2") (pintype "passive"))
      (node (ref "R4") (pin "1") (pinfunction "1_1") (pintype "passive"))
      (node (ref "U$1") (pin "IN+") (pinfunction "IN+_IN+") (pintype "bidirectional"))
      (node (ref "U$7") (pin "IN-") (pinfunction "IN-_IN-") (pintype "bidirectional"))
      (node (ref "U$8") (pin "-") (pinfunction "-_-") (pintype "bidirectional"))
      (node (ref "U$8") (pin "FB") (pinfunction "FB_FB") (pintype "bidirectional"))
      (node (ref "U$9") (pin "SOURCE") (pinfunction "SOURCE_SOURCE") (pintype "bidirectional"))
    )
    (net (code "52") (name "Net-(R13-Pad1)") (class "Default")
      (node (ref "R13") (pin "1") (pinfunction "1_1") (pintype "passive"))
      (node (ref "R14") (pin "2") (pinfunction "2_2") (pintype "passive"))
      (node (ref "U$7") (pin "V+") (pinfunction "V+_V+") (pintype "bidirectional"))
    )
    (net (code "53") (name "Net-(R15-Pad2)") (class "Default")
      (node (ref "R15") (pin "2") (pinfunction "2_2") (pintype "passive"))
      (node (ref "R16") (pin "1") (pinfunction "1_1") (pintype "passive"))
      (node (ref "U$8") (pin "+") (pinfunction "+_+") (pintype "bidirectional"))
    )
    (net (code "54") (name "Net-(R17-1)") (class "Default")
      (node (ref "R17") (pin "P$1") (pinfunction "1_P$1") (pintype "passive"))
      (node (ref "U$9") (pin "DRAIN") (pinfunction "DRAIN_DRAIN") (pintype "bidirectional"))
    )
    (net (code "55") (name "Net-(R17-2)") (class "Default")
      (node (ref "C5") (pin "+") (pinfunction "+_+") (pintype "bidirectional"))
      (node (ref "C7") (pin "-") (pinfunction "-_-") (pintype "bidirectional"))
      (node (ref "D4") (pin "C") (pinfunction "C_C") (pintype "passive"))
      (node (ref "R13") (pin "2") (pinfunction "2_2") (pintype "passive"))
      (node (ref "R15") (pin "1") (pinfunction "1_1") (pintype "passive"))
      (node (ref "R17") (pin "P$2") (pinfunction "2_P$2") (pintype "passive"))
      (node (ref "R20") (pin "1") (pinfunction "1_1") (pintype "passive"))
      (node (ref "U$10") (pin "IN-") (pinfunction "IN-_IN-") (pintype "bidirectional"))
      (node (ref "U$11") (pin "-") (pinfunction "-_-") (pintype "bidirectional"))
      (node (ref "U$11") (pin "FB") (pinfunction "FB_FB") (pintype "bidirectional"))
      (node (ref "U$12") (pin "SOURCE") (pinfunction "SOURCE_SOURCE") (pintype "bidirectional"))
      (node (ref "U$7") (pin "IN+") (pinfunction "IN+_IN+") (pintype "bidirectional"))
    )
    (net (code "56") (name "Net-(R19-Pad1)") (class "Default")
      (node (ref "R19") (pin "1") (pinfunction "1_1") (pintype "passive"))
      (node (ref "R20") (pin "2") (pinfunction "2_2") (pintype "passive"))
      (node (ref "U$10") (pin "V+") (pinfunction "V+_V+") (pintype "bidirectional"))
    )
    (net (code "57") (name "Net-(R21-Pad2)") (class "Default")
      (node (ref "R21") (pin "2") (pinfunction "2_2") (pintype "passive"))
      (node (ref "R22") (pin "1") (pinfunction "1_1") (pintype "passive"))
      (node (ref "U$11") (pin "+") (pinfunction "+_+") (pintype "bidirectional"))
    )
    (net (code "58") (name "Net-(R23-1)") (class "Default")
      (node (ref "R23") (pin "P$1") (pinfunction "1_P$1") (pintype "passive"))
      (node (ref "U$12") (pin "DRAIN") (pinfunction "DRAIN_DRAIN") (pintype "bidirectional"))
    )
    (net (code "59") (name "Net-(R23-2)") (class "Default")
      (node (ref "C7") (pin "+") (pinfunction "+_+") (pintype "bidirectional"))
      (node (ref "C9") (pin "-") (pinfunction "-_-") (pintype "bidirectional"))
      (node (ref "D5") (pin "C") (pinfunction "C_C") (pintype "passive"))
      (node (ref "R19") (pin "2") (pinfunction "2_2") (pintype "passive"))
      (node (ref "R21") (pin "1") (pinfunction "1_1") (pintype "passive"))
      (node (ref "R23") (pin "P$2") (pinfunction "2_P$2") (pintype "passive"))
      (node (ref "R26") (pin "1") (pinfunction "1_1") (pintype "passive"))
      (node (ref "U$10") (pin "IN+") (pinfunction "IN+_IN+") (pintype "bidirectional"))
      (node (ref "U$13") (pin "IN-") (pinfunction "IN-_IN-") (pintype "bidirectional"))
      (node (ref "U$14") (pin "-") (pinfunction "-_-") (pintype "bidirectional"))
      (node (ref "U$14") (pin "FB") (pinfunction "FB_FB") (pintype "bidirectional"))
      (node (ref "U$15") (pin "SOURCE") (pinfunction "SOURCE_SOURCE") (pintype "bidirectional"))
    )
    (net (code "60") (name "Net-(R25-Pad1)") (class "Default")
      (node (ref "R25") (pin "1") (pinfunction "1_1") (pintype "passive"))
      (node (ref "R26") (pin "2") (pinfunction "2_2") (pintype "passive"))
      (node (ref "U$13") (pin "V+") (pinfunction "V+_V+") (pintype "bidirectional"))
    )
    (net (code "61") (name "Net-(R27-Pad2)") (class "Default")
      (node (ref "R27") (pin "2") (pinfunction "2_2") (pintype "passive"))
      (node (ref "R28") (pin "1") (pinfunction "1_1") (pintype "passive"))
      (node (ref "U$14") (pin "+") (pinfunction "+_+") (pintype "bidirectional"))
    )
    (net (code "62") (name "Net-(R29-1)") (class "Default")
      (node (ref "R29") (pin "P$1") (pinfunction "1_P$1") (pintype "passive"))
      (node (ref "U$15") (pin "DRAIN") (pinfunction "DRAIN_DRAIN") (pintype "bidirectional"))
    )
    (net (code "63") (name "Net-(R29-2)") (class "Default")
      (node (ref "C11") (pin "-") (pinfunction "-_-") (pintype "bidirectional"))
      (node (ref "C9") (pin "+") (pinfunction "+_+") (pintype "bidirectional"))
      (node (ref "D6") (pin "C") (pinfunction "C_C") (pintype "passive"))
      (node (ref "R25") (pin "2") (pinfunction "2_2") (pintype "passive"))
      (node (ref "R27") (pin "1") (pinfunction "1_1") (pintype "passive"))
      (node (ref "R29") (pin "P$2") (pinfunction "2_P$2") (pintype "passive"))
      (node (ref "R32") (pin "1") (pinfunction "1_1") (pintype "passive"))
      (node (ref "U$13") (pin "IN+") (pinfunction "IN+_IN+") (pintype "bidirectional"))
      (node (ref "U$16") (pin "IN-") (pinfunction "IN-_IN-") (pintype "bidirectional"))
      (node (ref "U$17") (pin "-") (pinfunction "-_-") (pintype "bidirectional"))
      (node (ref "U$17") (pin "FB") (pinfunction "FB_FB") (pintype "bidirectional"))
      (node (ref "U$18") (pin "SOURCE") (pinfunction "SOURCE_SOURCE") (pintype "bidirectional"))
    )
    (net (code "64") (name "Net-(R31-Pad1)") (class "Default")
      (node (ref "R31") (pin "1") (pinfunction "1_1") (pintype "passive"))
      (node (ref "R32") (pin "2") (pinfunction "2_2") (pintype "passive"))
      (node (ref "U$16") (pin "V+") (pinfunction "V+_V+") (pintype "bidirectional"))
    )
    (net (code "65") (name "Net-(R33-Pad2)") (class "Default")
      (node (ref "R33") (pin "2") (pinfunction "2_2") (pintype "passive"))
      (node (ref "R34") (pin "1") (pinfunction "1_1") (pintype "passive"))
      (node (ref "U$17") (pin "+") (pinfunction "+_+") (pintype "bidirectional"))
    )
    (net (code "66") (name "Net-(R35-1)") (class "Default")
      (node (ref "R35") (pin "P$1") (pinfunction "1_P$1") (pintype "passive"))
      (node (ref "U$18") (pin "DRAIN") (pinfunction "DRAIN_DRAIN") (pintype "bidirectional"))
    )
    (net (code "67") (name "Net-(R35-2)") (class "Default")
      (node (ref "C11") (pin "+") (pinfunction "+_+") (pintype "bidirectional"))
      (node (ref "C13") (pin "-") (pinfunction "-_-") (pintype "bidirectional"))
      (node (ref "D7") (pin "C") (pinfunction "C_C") (pintype "passive"))
      (node (ref "R31") (pin "2") (pinfunction "2_2") (pintype "passive"))
      (node (ref "R33") (pin "1") (pinfunction "1_1") (pintype "passive"))
      (node (ref "R35") (pin "P$2") (pinfunction "2_P$2") (pintype "passive"))
      (node (ref "R38") (pin "1") (pinfunction "1_1") (pintype "passive"))
      (node (ref "U$16") (pin "IN+") (pinfunction "IN+_IN+") (pintype "bidirectional"))
      (node (ref "U$19") (pin "IN-") (pinfunction "IN-_IN-") (pintype "bidirectional"))
      (node (ref "U$20") (pin "-") (pinfunction "-_-") (pintype "bidirectional"))
      (node (ref "U$20") (pin "FB") (pinfunction "FB_FB") (pintype "bidirectional"))
      (node (ref "U$21") (pin "SOURCE") (pinfunction "SOURCE_SOURCE") (pintype "bidirectional"))
    )
    (net (code "68") (name "Net-(R37-Pad1)") (class "Default")
      (node (ref "R37") (pin "1") (pinfunction "1_1") (pintype "passive"))
      (node (ref "R38") (pin "2") (pinfunction "2_2") (pintype "passive"))
      (node (ref "U$19") (pin "V+") (pinfunction "V+_V+") (pintype "bidirectional"))
    )
    (net (code "69") (name "Net-(R39-Pad2)") (class "Default")
      (node (ref "R39") (pin "2") (pinfunction "2_2") (pintype "passive"))
      (node (ref "R40") (pin "1") (pinfunction "1_1") (pintype "passive"))
      (node (ref "U$20") (pin "+") (pinfunction "+_+") (pintype "bidirectional"))
    )
    (net (code "70") (name "Net-(R41-1)") (class "Default")
      (node (ref "R41") (pin "P$1") (pinfunction "1_P$1") (pintype "passive"))
      (node (ref "U$21") (pin "DRAIN") (pinfunction "DRAIN_DRAIN") (pintype "bidirectional"))
    )
    (net (code "71") (name "Net-(R41-2)") (class "Default")
      (node (ref "C13") (pin "+") (pinfunction "+_+") (pintype "bidirectional"))
      (node (ref "C15") (pin "-") (pinfunction "-_-") (pintype "bidirectional"))
      (node (ref "D8") (pin "C") (pinfunction "C_C") (pintype "passive"))
      (node (ref "R37") (pin "2") (pinfunction "2_2") (pintype "passive"))
      (node (ref "R39") (pin "1") (pinfunction "1_1") (pintype "passive"))
      (node (ref "R41") (pin "P$2") (pinfunction "2_P$2") (pintype "passive"))
      (node (ref "R44") (pin "1") (pinfunction "1_1") (pintype "passive"))
      (node (ref "U$19") (pin "IN+") (pinfunction "IN+_IN+") (pintype "bidirectional"))
      (node (ref "U$22") (pin "IN-") (pinfunction "IN-_IN-") (pintype "bidirectional"))
      (node (ref "U$23") (pin "-") (pinfunction "-_-") (pintype "bidirectional"))
      (node (ref "U$23") (pin "FB") (pinfunction "FB_FB") (pintype "bidirectional"))
      (node (ref "U$24") (pin "SOURCE") (pinfunction "SOURCE_SOURCE") (pintype "bidirectional"))
    )
    (net (code "72") (name "Net-(R43-Pad1)") (class "Default")
      (node (ref "R43") (pin "1") (pinfunction "1_1") (pintype "passive"))
      (node (ref "R44") (pin "2") (pinfunction "2_2") (pintype "passive"))
      (node (ref "U$22") (pin "V+") (pinfunction "V+_V+") (pintype "bidirectional"))
    )
    (net (code "73") (name "Net-(R45-Pad2)") (class "Default")
      (node (ref "R45") (pin "2") (pinfunction "2_2") (pintype "passive"))
      (node (ref "R46") (pin "1") (pinfunction "1_1") (pintype "passive"))
      (node (ref "U$23") (pin "+") (pinfunction "+_+") (pintype "bidirectional"))
    )
    (net (code "74") (name "Net-(R47-1)") (class "Default")
      (node (ref "R47") (pin "P$1") (pinfunction "1_P$1") (pintype "passive"))
      (node (ref "U$24") (pin "DRAIN") (pinfunction "DRAIN_DRAIN") (pintype "bidirectional"))
    )
    (net (code "75") (name "Net-(R47-2)") (class "Default")
      (node (ref "C15") (pin "+") (pinfunction "+_+") (pintype "bidirectional"))
      (node (ref "C17") (pin "-") (pinfunction "-_-") (pintype "bidirectional"))
      (node (ref "D9") (pin "C") (pinfunction "C_C") (pintype "passive"))
      (node (ref "R43") (pin "2") (pinfunction "2_2") (pintype "passive"))
      (node (ref "R45") (pin "1") (pinfunction "1_1") (pintype "passive"))
      (node (ref "R47") (pin "P$2") (pinfunction "2_P$2") (pintype "passive"))
      (node (ref "R50") (pin "1") (pinfunction "1_1") (pintype "passive"))
      (node (ref "U$22") (pin "IN+") (pinfunction "IN+_IN+") (pintype "bidirectional"))
      (node (ref "U$25") (pin "IN-") (pinfunction "IN-_IN-") (pintype "bidirectional"))
      (node (ref "U$26") (pin "-") (pinfunction "-_-") (pintype "bidirectional"))
      (node (ref "U$26") (pin "FB") (pinfunction "FB_FB") (pintype "bidirectional"))
      (node (ref "U$27") (pin "SOURCE") (pinfunction "SOURCE_SOURCE") (pintype "bidirectional"))
    )
    (net (code "76") (name "Net-(R49-Pad1)") (class "Default")
      (node (ref "R49") (pin "1") (pinfunction "1_1") (pintype "passive"))
      (node (ref "R50") (pin "2") (pinfunction "2_2") (pintype "passive"))
      (node (ref "U$25") (pin "V+") (pinfunction "V+_V+") (pintype "bidirectional"))
    )
    (net (code "77") (name "Net-(R51-Pad2)") (class "Default")
      (node (ref "R51") (pin "2") (pinfunction "2_2") (pintype "passive"))
      (node (ref "R52") (pin "1") (pinfunction "1_1") (pintype "passive"))
      (node (ref "U$26") (pin "+") (pinfunction "+_+") (pintype "bidirectional"))
    )
    (net (code "78") (name "Net-(R53-1)") (class "Default")
      (node (ref "R53") (pin "P$1") (pinfunction "1_P$1") (pintype "passive"))
      (node (ref "U$27") (pin "DRAIN") (pinfunction "DRAIN_DRAIN") (pintype "bidirectional"))
    )
    (net (code "79") (name "Net-(R62-Pad2)") (class "Default")
      (node (ref "R62") (pin "2") (pinfunction "2_2") (pintype "passive"))
      (node (ref "R64") (pin "1") (pinfunction "1_1") (pintype "passive"))
      (node (ref "U$38") (pin "13") (pinfunction "13_13") (pintype "bidirectional"))
    )
    (net (code "80") (name "Net-(R63-Pad1)") (class "Default")
      (node (ref "R63") (pin "1") (pinfunction "1_1") (pintype "passive"))
      (node (ref "U$28") (pin "B") (pinfunction "B_B") (pintype "bidirectional"))
    )
    (net (code "81") (name "Net-(R63-Pad2)") (class "Default")
      (node (ref "R63") (pin "2") (pinfunction "2_2") (pintype "passive"))
      (node (ref "U$38") (pin "12") (pinfunction "12_12") (pintype "bidirectional"))
    )
    (net (code "82") (name "Net-(R64-Pad2)") (class "Default")
      (node (ref "R64") (pin "2") (pinfunction "2_2") (pintype "passive"))
      (node (ref "U$29") (pin "B") (pinfunction "B_B") (pintype "bidirectional"))
    )
    (net (code "83") (name "Net-(R65-Pad1)") (class "Default")
      (node (ref "R65") (pin "1") (pinfunction "1_1") (pintype "passive"))
      (node (ref "U$34") (pin "B") (pinfunction "B_B") (pintype "bidirectional"))
    )
    (net (code "84") (name "Net-(R65-Pad2)") (class "Default")
      (node (ref "R65") (pin "2") (pinfunction "2_2") (pintype "passive"))
      (node (ref "U$38") (pin "11") (pinfunction "11_11") (pintype "bidirectional"))
    )
    (net (code "85") (name "Net-(U$35-A-7)") (class "Default")
      (node (ref "R55") (pin "2") (pinfunction "2_2") (pintype "passive"))
      (node (ref "U$35") (pin "7") (pinfunction "A-7_7") (pintype "bidirectional"))
      (node (ref "U$36") (pin "7") (pinfunction "A-7_7") (pintype "bidirectional"))
      (node (ref "U$37") (pin "7") (pinfunction "A-7_7") (pintype "bidirectional"))
    )
    (net (code "86") (name "Net-(U$35-B-6)") (class "Default")
      (node (ref "R56") (pin "2") (pinfunction "2_2") (pintype "passive"))
      (node (ref "U$35") (pin "6") (pinfunction "B-6_6") (pintype "bidirectional"))
      (node (ref "U$36") (pin "6") (pinfunction "B-6_6") (pintype "bidirectional"))
      (node (ref "U$37") (pin "6") (pinfunction "B-6_6") (pintype "bidirectional"))
    )
    (net (code "87") (name "Net-(U$35-C-4)") (class "Default")
      (node (ref "R57") (pin "2") (pinfunction "2_2") (pintype "passive"))
      (node (ref "U$35") (pin "4") (pinfunction "C-4_4") (pintype "bidirectional"))
      (node (ref "U$36") (pin "4") (pinfunction "C-4_4") (pintype "bidirectional"))
      (node (ref "U$37") (pin "4") (pinfunction "C-4_4") (pintype "bidirectional"))
    )
    (net (code "88") (name "Net-(U$35-D-2)") (class "Default")
      (node (ref "R58") (pin "2") (pinfunction "2_2") (pintype "passive"))
      (node (ref "U$35") (pin "2") (pinfunction "D-2_2") (pintype "bidirectional"))
      (node (ref "U$36") (pin "2") (pinfunction "D-2_2") (pintype "bidirectional"))
      (node (ref "U$37") (pin "2") (pinfunction "D-2_2") (pintype "bidirectional"))
    )
    (net (code "89") (name "Net-(U$35-E-1)") (class "Default")
      (node (ref "R59") (pin "2") (pinfunction "2_2") (pintype "passive"))
      (node (ref "U$35") (pin "1") (pinfunction "E-1_1") (pintype "bidirectional"))
      (node (ref "U$36") (pin "1") (pinfunction "E-1_1") (pintype "bidirectional"))
      (node (ref "U$37") (pin "1") (pinfunction "E-1_1") (pintype "bidirectional"))
    )
    (net (code "90") (name "Net-(U$35-F-9)") (class "Default")
      (node (ref "R60") (pin "2") (pinfunction "2_2") (pintype "passive"))
      (node (ref "U$35") (pin "9") (pinfunction "F-9_9") (pintype "bidirectional"))
      (node (ref "U$36") (pin "9") (pinfunction "F-9_9") (pintype "bidirectional"))
      (node (ref "U$37") (pin "9") (pinfunction "F-9_9") (pintype "bidirectional"))
    )
    (net (code "91") (name "Net-(U$35-G-10)") (class "Default")
      (node (ref "R61") (pin "2") (pinfunction "2_2") (pintype "passive"))
      (node (ref "U$35") (pin "10") (pinfunction "G-10_10") (pintype "bidirectional"))
      (node (ref "U$36") (pin "10") (pinfunction "G-10_10") (pintype "bidirectional"))
      (node (ref "U$37") (pin "10") (pinfunction "G-10_10") (pintype "bidirectional"))
    )
    (net (code "92") (name "Net-(U$35-G1-3)") (class "Default")
      (node (ref "U$28") (pin "C") (pinfunction "C_C") (pintype "bidirectional"))
      (node (ref "U$28") (pin "C2") (pinfunction "C_C2") (pintype "bidirectional"))
      (node (ref "U$35") (pin "3") (pinfunction "G1-3_3") (pintype "bidirectional"))
      (node (ref "U$35") (pin "8") (pinfunction "G2-8_8") (pintype "bidirectional"))
    )
    (net (code "93") (name "Net-(U$36-G1-3)") (class "Default")
      (node (ref "U$34") (pin "C") (pinfunction "C_C") (pintype "bidirectional"))
      (node (ref "U$34") (pin "C2") (pinfunction "C_C2") (pintype "bidirectional"))
      (node (ref "U$36") (pin "3") (pinfunction "G1-3_3") (pintype "bidirectional"))
      (node (ref "U$36") (pin "8") (pinfunction "G2-8_8") (pintype "bidirectional"))
    )
    (net (code "94") (name "Net-(U$37-DP-5)") (class "Default")
      (node (ref "R62") (pin "1") (pinfunction "1_1") (pintype "passive"))
      (node (ref "U$37") (pin "5") (pinfunction "DP-5_5") (pintype "bidirectional"))
    )
    (net (code "95") (name "Net-(U$37-G1-3)") (class "Default")
      (node (ref "U$29") (pin "C") (pinfunction "C_C") (pintype "bidirectional"))
      (node (ref "U$29") (pin "C2") (pinfunction "C_C2") (pintype "bidirectional"))
      (node (ref "U$37") (pin "3") (pinfunction "G1-3_3") (pintype "bidirectional"))
      (node (ref "U$37") (pin "8") (pinfunction "G2-8_8") (pintype "bidirectional"))
    )
    (net (code "96") (name "Net-(VR1-CW)") (class "Default")
      (node (ref "C19") (pin "1") (pinfunction "1_1") (pintype "passive"))
      (node (ref "D10") (pin "C") (pinfunction "C_C") (pintype "passive"))
      (node (ref "R66") (pin "2") (pinfunction "2_2") (pintype "passive"))
      (node (ref "U$38") (pin "3") (pinfunction "3_3") (pintype "bidirectional"))
      (node (ref "VR1") (pin "1") (pinfunction "CW_1") (pintype "passive"))
    )
    (net (code "97") (name "SW") (class "Default")
      (node (ref "3.3V_BUCK") (pin "1") (pinfunction "SW_1") (pintype "bidirectional"))
      (node (ref "C20") (pin "2") (pinfunction "2_2") (pintype "passive"))
      (node (ref "D11") (pin "C") (pinfunction "C_C") (pintype "passive"))
      (node (ref "U$39") (pin "P$1") (pinfunction "P$1_P$1") (pintype "bidirectional"))
    )
    (net (code "98") (name "VCC") (class "Default")
      (node (ref "3.3V_BUCK") (pin "7") (pinfunction "VIN_7") (pintype "bidirectional"))
      (node (ref "C17") (pin "+") (pinfunction "+_+") (pintype "bidirectional"))
      (node (ref "C23") (pin "1") (pinfunction "1_1") (pintype "passive"))
      (node (ref "CHARGE") (pin "1") (pinfunction "VCC_1") (pintype "bidirectional"))
      (node (ref "MTR") (pin "1") (pinfunction "VCC_1") (pintype "bidirectional"))
      (node (ref "R49") (pin "2") (pinfunction "2_2") (pintype "passive"))
      (node (ref "R51") (pin "1") (pinfunction "1_1") (pintype "passive"))
      (node (ref "R53") (pin "P$2") (pinfunction "2_P$2") (pintype "passive"))
      (node (ref "R66") (pin "1") (pinfunction "1_1") (pintype "passive"))
      (node (ref "R68") (pin "2") (pinfunction "2_2") (pintype "passive"))
      (node (ref "U$25") (pin "IN+") (pinfunction "IN+_IN+") (pintype "bidirectional"))
    )
    (net (code "99") (name "unconnected-(U$35-DP-5-Pad5)") (class "Default")
      (node (ref "U$35") (pin "5") (pinfunction "DP-5_5") (pintype "bidirectional"))
    )
    (net (code "100") (name "unconnected-(U$36-DP-5-Pad5)") (class "Default")
      (node (ref "U$36") (pin "5") (pinfunction "DP-5_5") (pintype "bidirectional"))
    )
    (net (code "101") (name "unconnected-(U$38-Pad4)") (class "Default")
      (node (ref "U$38") (pin "4") (pinfunction "4_4") (pintype "bidirectional"))
    )
  )
)
